# boot.net
KiCad netlist of a schematic drawn in Altium Designer
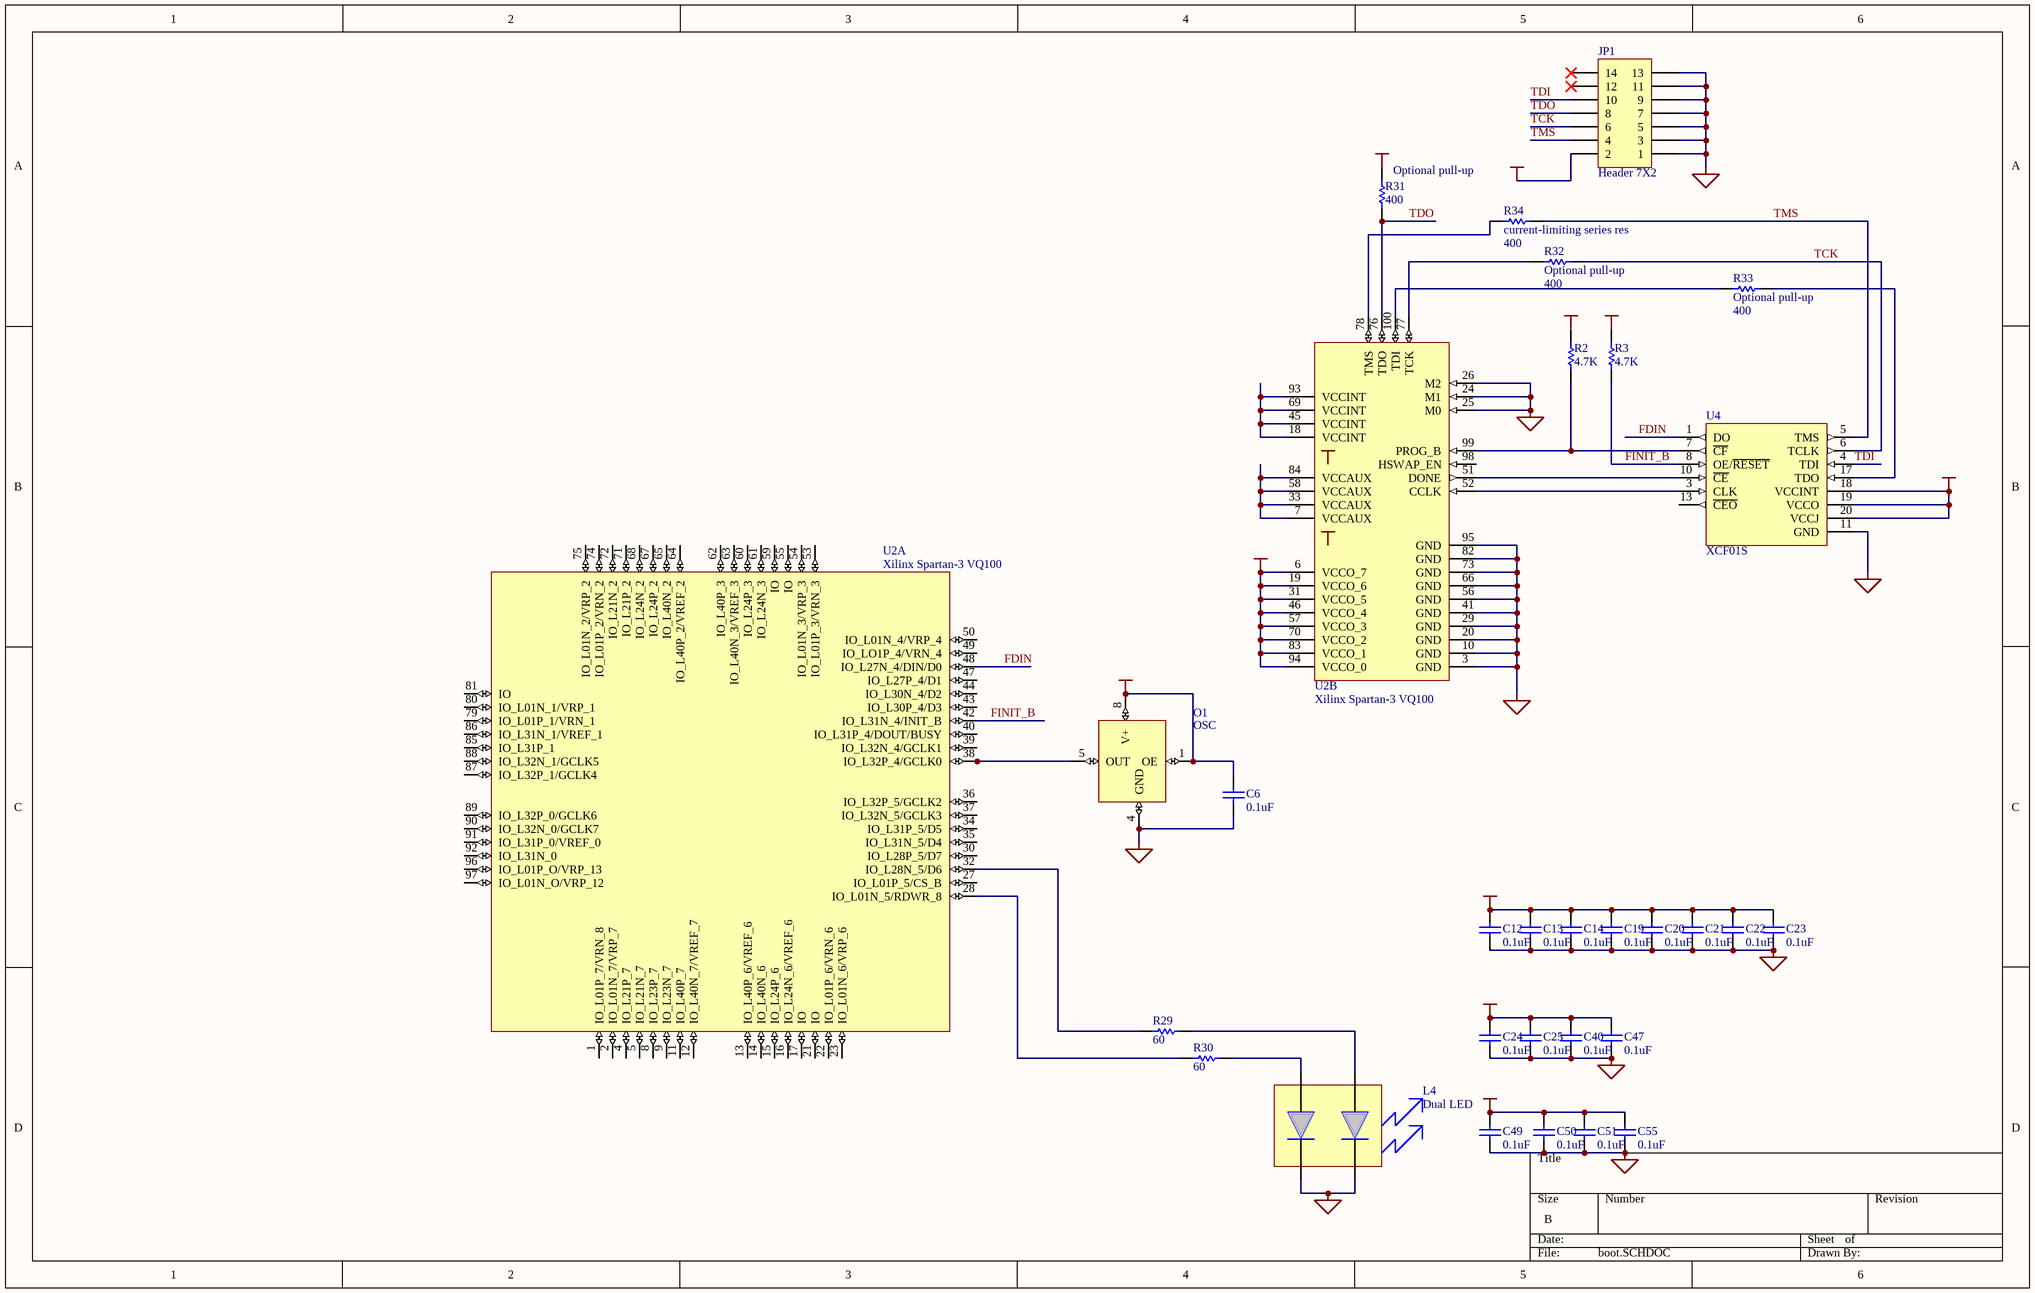
[diagram p0: boot.SCHDOC]

(export (version "E")
  (design (tool "Eeschema 10.0.6"))
  (components
    (comp (ref "C6")
      (value "Cap")
      (footprint "CC1608-0603")
      (description "Capacitor")
      (fields
        (field (name "MANUFACTURER") "Generic Components")
        (field (name "ALTIUM_VALUE") "0.1uF")
        (field (name "PUBLISHER") "Altium Limited")
      )
      (libsource (lib "Miscellaneous Devices") (part "Cap"))
    )
    (comp (ref "C12")
      (value "Cap")
      (footprint "CC1608-0603")
      (description "Capacitor")
      (fields
        (field (name "MANUFACTURER") "Generic Components")
        (field (name "ALTIUM_VALUE") "0.1uF")
        (field (name "PUBLISHER") "Altium Limited")
      )
      (libsource (lib "Miscellaneous Devices") (part "Cap"))
    )
    (comp (ref "C13")
      (value "Cap")
      (footprint "CC1608-0603")
      (description "Capacitor")
      (fields
        (field (name "MANUFACTURER") "Generic Components")
        (field (name "ALTIUM_VALUE") "0.1uF")
        (field (name "PUBLISHER") "Altium Limited")
      )
      (libsource (lib "Miscellaneous Devices") (part "Cap"))
    )
    (comp (ref "C14")
      (value "Cap")
      (footprint "CC1608-0603")
      (description "Capacitor")
      (fields
        (field (name "MANUFACTURER") "Generic Components")
        (field (name "ALTIUM_VALUE") "0.1uF")
        (field (name "PUBLISHER") "Altium Limited")
      )
      (libsource (lib "Miscellaneous Devices") (part "Cap"))
    )
    (comp (ref "C19")
      (value "Cap")
      (footprint "CC1608-0603")
      (description "Capacitor")
      (fields
        (field (name "MANUFACTURER") "Generic Components")
        (field (name "ALTIUM_VALUE") "0.1uF")
        (field (name "PUBLISHER") "Altium Limited")
      )
      (libsource (lib "Miscellaneous Devices") (part "Cap"))
    )
    (comp (ref "C20")
      (value "Cap")
      (footprint "CC1608-0603")
      (description "Capacitor")
      (fields
        (field (name "MANUFACTURER") "Generic Components")
        (field (name "ALTIUM_VALUE") "0.1uF")
        (field (name "PUBLISHER") "Altium Limited")
      )
      (libsource (lib "Miscellaneous Devices") (part "Cap"))
    )
    (comp (ref "C21")
      (value "Cap")
      (footprint "CC1608-0603")
      (description "Capacitor")
      (fields
        (field (name "MANUFACTURER") "Generic Components")
        (field (name "ALTIUM_VALUE") "0.1uF")
        (field (name "PUBLISHER") "Altium Limited")
      )
      (libsource (lib "Miscellaneous Devices") (part "Cap"))
    )
    (comp (ref "C22")
      (value "Cap")
      (footprint "CC1608-0603")
      (description "Capacitor")
      (fields
        (field (name "MANUFACTURER") "Generic Components")
        (field (name "ALTIUM_VALUE") "0.1uF")
        (field (name "PUBLISHER") "Altium Limited")
      )
      (libsource (lib "Miscellaneous Devices") (part "Cap"))
    )
    (comp (ref "C23")
      (value "Cap")
      (footprint "CC1608-0603")
      (description "Capacitor")
      (fields
        (field (name "MANUFACTURER") "Generic Components")
        (field (name "ALTIUM_VALUE") "0.1uF")
        (field (name "PUBLISHER") "Altium Limited")
      )
      (libsource (lib "Miscellaneous Devices") (part "Cap"))
    )
    (comp (ref "C24")
      (value "Cap")
      (footprint "CC1608-0603")
      (description "Capacitor")
      (fields
        (field (name "MANUFACTURER") "Generic Components")
        (field (name "ALTIUM_VALUE") "0.1uF")
        (field (name "PUBLISHER") "Altium Limited")
      )
      (libsource (lib "Miscellaneous Devices") (part "Cap"))
    )
    (comp (ref "C25")
      (value "Cap")
      (footprint "CC1608-0603")
      (description "Capacitor")
      (fields
        (field (name "MANUFACTURER") "Generic Components")
        (field (name "ALTIUM_VALUE") "0.1uF")
        (field (name "PUBLISHER") "Altium Limited")
      )
      (libsource (lib "Miscellaneous Devices") (part "Cap"))
    )
    (comp (ref "C40")
      (value "Cap")
      (footprint "CC1608-0603")
      (description "Capacitor")
      (fields
        (field (name "MANUFACTURER") "Generic Components")
        (field (name "ALTIUM_VALUE") "0.1uF")
        (field (name "PUBLISHER") "Altium Limited")
      )
      (libsource (lib "Miscellaneous Devices") (part "Cap"))
    )
    (comp (ref "C47")
      (value "Cap")
      (footprint "CC1608-0603")
      (description "Capacitor")
      (fields
        (field (name "MANUFACTURER") "Generic Components")
        (field (name "ALTIUM_VALUE") "0.1uF")
        (field (name "PUBLISHER") "Altium Limited")
      )
      (libsource (lib "Miscellaneous Devices") (part "Cap"))
    )
    (comp (ref "C49")
      (value "Cap")
      (footprint "CC1608-0603")
      (description "Capacitor")
      (fields
        (field (name "MANUFACTURER") "Generic Components")
        (field (name "ALTIUM_VALUE") "0.1uF")
        (field (name "PUBLISHER") "Altium Limited")
      )
      (libsource (lib "Miscellaneous Devices") (part "Cap"))
    )
    (comp (ref "C50")
      (value "Cap")
      (footprint "CC1608-0603")
      (description "Capacitor")
      (fields
        (field (name "MANUFACTURER") "Generic Components")
        (field (name "ALTIUM_VALUE") "0.1uF")
        (field (name "PUBLISHER") "Altium Limited")
      )
      (libsource (lib "Miscellaneous Devices") (part "Cap"))
    )
    (comp (ref "C51")
      (value "Cap")
      (footprint "CC1608-0603")
      (description "Capacitor")
      (fields
        (field (name "MANUFACTURER") "Generic Components")
        (field (name "ALTIUM_VALUE") "0.1uF")
        (field (name "PUBLISHER") "Altium Limited")
      )
      (libsource (lib "Miscellaneous Devices") (part "Cap"))
    )
    (comp (ref "C55")
      (value "Cap")
      (footprint "CC1608-0603")
      (description "Capacitor")
      (fields
        (field (name "MANUFACTURER") "Generic Components")
        (field (name "ALTIUM_VALUE") "0.1uF")
        (field (name "PUBLISHER") "Altium Limited")
      )
      (libsource (lib "Miscellaneous Devices") (part "Cap"))
    )
    (comp (ref "JP1")
      (value "Header 7X2")
      (footprint "HDR2X7")
      (description "Header, 7-Pin, Dual row")
      (fields (field (name "MANUFACTURER") "Generic Components") (field (name "PUBLISHER") "Altium Limited"))
      (libsource (lib "Miscellaneous Connectors") (part "Header 7X2"))
    )
    (comp (ref "L4")
      (value "Dual LED")
      (footprint "LUMEX DUAL RT-ANG LED")
      (description "DUAL LED")
      (libsource (lib "My devices") (part "DUAL LED"))
    )
    (comp (ref "O1")
      (value "OSC")
      (footprint "SG636PCE")
      (description "Epson CMOS/TTL Oscillator")
      (libsource (lib "My devices") (part "OSC"))
    )
    (comp (ref "R2")
      (value "Res1")
      (footprint "CC1608-0603")
      (description "Resistor")
      (fields
        (field (name "MANUFACTURER") "Generic Components")
        (field (name "ALTIUM_VALUE") "4.7K")
        (field (name "PUBLISHER") "Altium Limited")
      )
      (libsource (lib "Miscellaneous Devices") (part "Res1"))
    )
    (comp (ref "R3")
      (value "Res1")
      (footprint "CC1608-0603")
      (description "Resistor")
      (fields
        (field (name "MANUFACTURER") "Generic Components")
        (field (name "ALTIUM_VALUE") "4.7K")
        (field (name "PUBLISHER") "Altium Limited")
      )
      (libsource (lib "Miscellaneous Devices") (part "Res1"))
    )
    (comp (ref "R29")
      (value "Res1")
      (footprint "R2012-0805")
      (description "Resistor")
      (fields
        (field (name "MANUFACTURER") "Generic Components")
        (field (name "ALTIUM_VALUE") "60")
        (field (name "PUBLISHER") "Altium Limited")
      )
      (libsource (lib "Miscellaneous Devices") (part "Res1"))
    )
    (comp (ref "R30")
      (value "Res1")
      (footprint "R2012-0805")
      (description "Resistor")
      (fields
        (field (name "MANUFACTURER") "Generic Components")
        (field (name "ALTIUM_VALUE") "60")
        (field (name "PUBLISHER") "Altium Limited")
      )
      (libsource (lib "Miscellaneous Devices") (part "Res1"))
    )
    (comp (ref "R31")
      (value "Optional pull-up")
      (footprint "CC1608-0603")
      (description "Resistor")
      (fields
        (field (name "MANUFACTURER") "Generic Components")
        (field (name "ALTIUM_VALUE") "400")
        (field (name "PUBLISHER") "Altium Limited")
      )
      (libsource (lib "Miscellaneous Devices") (part "Res1"))
    )
    (comp (ref "R32")
      (value "Optional pull-up")
      (footprint "CC1608-0603")
      (description "Resistor")
      (fields
        (field (name "MANUFACTURER") "Generic Components")
        (field (name "ALTIUM_VALUE") "400")
        (field (name "PUBLISHER") "Altium Limited")
      )
      (libsource (lib "Miscellaneous Devices") (part "Res1"))
    )
    (comp (ref "R33")
      (value "Optional pull-up")
      (footprint "CC1608-0603")
      (description "Resistor")
      (fields
        (field (name "MANUFACTURER") "Generic Components")
        (field (name "ALTIUM_VALUE") "400")
        (field (name "PUBLISHER") "Altium Limited")
      )
      (libsource (lib "Miscellaneous Devices") (part "Res1"))
    )
    (comp (ref "R34")
      (value "current-limiting series res")
      (footprint "CC1608-0603")
      (description "Resistor")
      (fields
        (field (name "MANUFACTURER") "Generic Components")
        (field (name "ALTIUM_VALUE") "400")
        (field (name "PUBLISHER") "Altium Limited")
      )
      (libsource (lib "Miscellaneous Devices") (part "Res1"))
    )
    (comp (ref "U2")
      (value "Xilinx Spartan-3 VQ100")
      (footprint "F-QFP14X14-G100/N")
      (libsource (lib "") (part "XC3S50-VQ100_1"))
    )
    (comp (ref "U4")
      (value "XCF01S")
      (footprint "TSSO6x6-G20/X.3")
      (description "Xilinx Platform Flash")
      (libsource (lib "My devices") (part "XCF01S"))
    )
  )
  (nets
    (net (code "1") (name "+1.2VCC") (class "Default")
      (node (ref "C24") (pin "1") (pinfunction "1_1") (pintype "passive"))
      (node (ref "C25") (pin "1") (pinfunction "1_1") (pintype "passive"))
      (node (ref "C40") (pin "1") (pinfunction "1_1") (pintype "passive"))
      (node (ref "C47") (pin "1") (pinfunction "1_1") (pintype "passive"))
    )
    (net (code "2") (name "+2.5VCC") (class "Default")
      (node (ref "C49") (pin "1") (pinfunction "1_1") (pintype "passive"))
      (node (ref "C50") (pin "1") (pinfunction "1_1") (pintype "passive"))
      (node (ref "C51") (pin "1") (pinfunction "1_1") (pintype "passive"))
      (node (ref "C55") (pin "1") (pinfunction "1_1") (pintype "passive"))
    )
    (net (code "3") (name "/FDIN") (class "Default")
      (node (ref "U2") (pin "48") (pinfunction "IO_L27N_4/DIN/D0_48") (pintype "bidirectional"))
      (node (ref "U4") (pin "1") (pinfunction "DO_1") (pintype "output"))
    )
    (net (code "4") (name "/FINIT_B") (class "Default")
      (node (ref "R3") (pin "1") (pinfunction "1_1") (pintype "passive"))
      (node (ref "U2") (pin "42") (pinfunction "IO_L31N_4/INIT_B_42") (pintype "bidirectional"))
      (node (ref "U4") (pin "8") (pinfunction "OE/~{RESET}_8") (pintype "input"))
    )
    (net (code "5") (name "/TCK") (class "Default")
      (node (ref "JP1") (pin "6") (pinfunction "6_6") (pintype "passive"))
      (node (ref "R32") (pin "1") (pinfunction "1_1") (pintype "passive"))
      (node (ref "U4") (pin "6") (pinfunction "TCLK_6") (pintype "output"))
    )
    (net (code "6") (name "/TDI") (class "Default")
      (node (ref "JP1") (pin "10") (pinfunction "10_10") (pintype "passive"))
      (node (ref "U4") (pin "4") (pinfunction "TDI_4") (pintype "input"))
    )
    (net (code "7") (name "/TDO") (class "Default")
      (node (ref "JP1") (pin "8") (pinfunction "8_8") (pintype "passive"))
      (node (ref "R31") (pin "1") (pinfunction "1_1") (pintype "passive"))
      (node (ref "U2") (pin "76") (pinfunction "TDO_76") (pintype "bidirectional"))
    )
    (net (code "8") (name "/TMS") (class "Default")
      (node (ref "JP1") (pin "4") (pinfunction "4_4") (pintype "passive"))
      (node (ref "R34") (pin "1") (pinfunction "1_1") (pintype "passive"))
      (node (ref "U4") (pin "5") (pinfunction "TMS_5") (pintype "output"))
    )
    (net (code "9") (name "GND") (class "Default")
      (node (ref "C12") (pin "2") (pinfunction "2_2") (pintype "passive"))
      (node (ref "C13") (pin "2") (pinfunction "2_2") (pintype "passive"))
      (node (ref "C14") (pin "2") (pinfunction "2_2") (pintype "passive"))
      (node (ref "C19") (pin "2") (pinfunction "2_2") (pintype "passive"))
      (node (ref "C20") (pin "2") (pinfunction "2_2") (pintype "passive"))
      (node (ref "C21") (pin "2") (pinfunction "2_2") (pintype "passive"))
      (node (ref "C22") (pin "2") (pinfunction "2_2") (pintype "passive"))
      (node (ref "C23") (pin "2") (pinfunction "2_2") (pintype "passive"))
      (node (ref "C24") (pin "2") (pinfunction "2_2") (pintype "passive"))
      (node (ref "C25") (pin "2") (pinfunction "2_2") (pintype "passive"))
      (node (ref "C40") (pin "2") (pinfunction "2_2") (pintype "passive"))
      (node (ref "C47") (pin "2") (pinfunction "2_2") (pintype "passive"))
      (node (ref "C49") (pin "2") (pinfunction "2_2") (pintype "passive"))
      (node (ref "C50") (pin "2") (pinfunction "2_2") (pintype "passive"))
      (node (ref "C51") (pin "2") (pinfunction "2_2") (pintype "passive"))
      (node (ref "C55") (pin "2") (pinfunction "2_2") (pintype "passive"))
      (node (ref "C6") (pin "2") (pinfunction "2_2") (pintype "passive"))
      (node (ref "JP1") (pin "1") (pinfunction "1_1") (pintype "passive"))
      (node (ref "JP1") (pin "11") (pinfunction "11_11") (pintype "passive"))
      (node (ref "JP1") (pin "13") (pinfunction "13_13") (pintype "passive"))
      (node (ref "JP1") (pin "3") (pinfunction "3_3") (pintype "passive"))
      (node (ref "JP1") (pin "5") (pinfunction "5_5") (pintype "passive"))
      (node (ref "JP1") (pin "7") (pinfunction "7_7") (pintype "passive"))
      (node (ref "JP1") (pin "9") (pinfunction "9_9") (pintype "passive"))
      (node (ref "L4") (pin "2") (pinfunction "2_2") (pintype "passive"))
      (node (ref "L4") (pin "4") (pinfunction "C2_4") (pintype "passive"))
      (node (ref "O1") (pin "4") (pinfunction "GND_4") (pintype "bidirectional"))
      (node (ref "U2") (pin "10") (pinfunction "GND_10") (pintype "power_in"))
      (node (ref "U2") (pin "20") (pinfunction "GND_20") (pintype "power_in"))
      (node (ref "U2") (pin "24") (pinfunction "M1_24") (pintype "input"))
      (node (ref "U2") (pin "25") (pinfunction "M0_25") (pintype "input"))
      (node (ref "U2") (pin "26") (pinfunction "M2_26") (pintype "input"))
      (node (ref "U2") (pin "29") (pinfunction "GND_29") (pintype "power_in"))
      (node (ref "U2") (pin "3") (pinfunction "GND_3") (pintype "power_in"))
      (node (ref "U2") (pin "41") (pinfunction "GND_41") (pintype "power_in"))
      (node (ref "U2") (pin "56") (pinfunction "GND_56") (pintype "power_in"))
      (node (ref "U2") (pin "66") (pinfunction "GND_66") (pintype "power_in"))
      (node (ref "U2") (pin "73") (pinfunction "GND_73") (pintype "power_in"))
      (node (ref "U2") (pin "82") (pinfunction "GND_82") (pintype "power_in"))
      (node (ref "U2") (pin "95") (pinfunction "GND_95") (pintype "power_in"))
      (node (ref "U4") (pin "11") (pinfunction "GND_11") (pintype "power_in"))
    )
    (net (code "10") (name "Net-(L4-A1)") (class "Default")
      (node (ref "L4") (pin "1") (pinfunction "A1_1") (pintype "passive"))
      (node (ref "R30") (pin "1") (pinfunction "1_1") (pintype "passive"))
    )
    (net (code "11") (name "Net-(L4-A2)") (class "Default")
      (node (ref "L4") (pin "3") (pinfunction "A2_3") (pintype "passive"))
      (node (ref "R29") (pin "1") (pinfunction "1_1") (pintype "passive"))
    )
    (net (code "12") (name "Net-(O1-OUT)") (class "Default")
      (node (ref "O1") (pin "5") (pinfunction "OUT_5") (pintype "bidirectional"))
      (node (ref "U2") (pin "38") (pinfunction "IO_L32P_4/GCLK0_38") (pintype "bidirectional"))
    )
    (net (code "13") (name "Net-(U2A-IO_L01N_5{slash}RDWR_8)") (class "Default")
      (node (ref "R30") (pin "2") (pinfunction "2_2") (pintype "passive"))
      (node (ref "U2") (pin "28") (pinfunction "IO_L01N_5/RDWR_8_28") (pintype "bidirectional"))
    )
    (net (code "14") (name "Net-(U2A-IO_L28N_5{slash}D6)") (class "Default")
      (node (ref "R29") (pin "2") (pinfunction "2_2") (pintype "passive"))
      (node (ref "U2") (pin "32") (pinfunction "IO_L28N_5/D6_32") (pintype "bidirectional"))
    )
    (net (code "15") (name "Net-(U2B-CCLK)") (class "Default")
      (node (ref "U2") (pin "52") (pinfunction "CCLK_52") (pintype "input"))
      (node (ref "U4") (pin "3") (pinfunction "CLK_3") (pintype "input"))
    )
    (net (code "16") (name "Net-(U2B-DONE)") (class "Default")
      (node (ref "U2") (pin "51") (pinfunction "DONE_51") (pintype "output"))
      (node (ref "U4") (pin "10") (pinfunction "~{CE}_10") (pintype "input"))
    )
    (net (code "17") (name "Net-(U2B-PROG_B)") (class "Default")
      (node (ref "R2") (pin "1") (pinfunction "1_1") (pintype "passive"))
      (node (ref "U2") (pin "99") (pinfunction "PROG_B_99") (pintype "input"))
      (node (ref "U4") (pin "7") (pinfunction "~{CF}_7") (pintype "output"))
    )
    (net (code "18") (name "Net-(U2B-TCK)") (class "Default")
      (node (ref "R32") (pin "2") (pinfunction "2_2") (pintype "passive"))
      (node (ref "U2") (pin "77") (pinfunction "TCK_77") (pintype "bidirectional"))
    )
    (net (code "19") (name "Net-(U2B-TDI)") (class "Default")
      (node (ref "R33") (pin "2") (pinfunction "2_2") (pintype "passive"))
      (node (ref "U2") (pin "100") (pinfunction "TDI_100") (pintype "bidirectional"))
    )
    (net (code "20") (name "Net-(U2B-TMS)") (class "Default")
      (node (ref "R34") (pin "2") (pinfunction "2_2") (pintype "passive"))
      (node (ref "U2") (pin "78") (pinfunction "TMS_78") (pintype "bidirectional"))
    )
    (net (code "21") (name "Net-(U2B-VCCAUX-Pad33)") (class "Default")
      (node (ref "U2") (pin "33") (pinfunction "VCCAUX_33") (pintype "power_in"))
      (node (ref "U2") (pin "58") (pinfunction "VCCAUX_58") (pintype "power_in"))
      (node (ref "U2") (pin "7") (pinfunction "VCCAUX_7") (pintype "power_in"))
      (node (ref "U2") (pin "84") (pinfunction "VCCAUX_84") (pintype "power_in"))
    )
    (net (code "22") (name "Net-(U2B-VCCINT-Pad18)") (class "Default")
      (node (ref "U2") (pin "18") (pinfunction "VCCINT_18") (pintype "power_in"))
      (node (ref "U2") (pin "45") (pinfunction "VCCINT_45") (pintype "power_in"))
      (node (ref "U2") (pin "69") (pinfunction "VCCINT_69") (pintype "power_in"))
      (node (ref "U2") (pin "93") (pinfunction "VCCINT_93") (pintype "power_in"))
    )
    (net (code "23") (name "Net-(U4-TDO)") (class "Default")
      (node (ref "R33") (pin "1") (pinfunction "1_1") (pintype "passive"))
      (node (ref "U4") (pin "17") (pinfunction "TDO_17") (pintype "input"))
    )
    (net (code "24") (name "VCC") (class "Default")
      (node (ref "C12") (pin "1") (pinfunction "1_1") (pintype "passive"))
      (node (ref "C13") (pin "1") (pinfunction "1_1") (pintype "passive"))
      (node (ref "C14") (pin "1") (pinfunction "1_1") (pintype "passive"))
      (node (ref "C19") (pin "1") (pinfunction "1_1") (pintype "passive"))
      (node (ref "C20") (pin "1") (pinfunction "1_1") (pintype "passive"))
      (node (ref "C21") (pin "1") (pinfunction "1_1") (pintype "passive"))
      (node (ref "C22") (pin "1") (pinfunction "1_1") (pintype "passive"))
      (node (ref "C23") (pin "1") (pinfunction "1_1") (pintype "passive"))
      (node (ref "C6") (pin "1") (pinfunction "1_1") (pintype "passive"))
      (node (ref "JP1") (pin "2") (pinfunction "2_2") (pintype "passive"))
      (node (ref "O1") (pin "1") (pinfunction "OE_1") (pintype "bidirectional"))
      (node (ref "O1") (pin "8") (pinfunction "V+_8") (pintype "bidirectional"))
      (node (ref "R2") (pin "2") (pinfunction "2_2") (pintype "passive"))
      (node (ref "R3") (pin "2") (pinfunction "2_2") (pintype "passive"))
      (node (ref "R31") (pin "2") (pinfunction "2_2") (pintype "passive"))
      (node (ref "U2") (pin "19") (pinfunction "VCCO_6_19") (pintype "power_in"))
      (node (ref "U2") (pin "31") (pinfunction "VCCO_5_31") (pintype "power_in"))
      (node (ref "U2") (pin "46") (pinfunction "VCCO_4_46") (pintype "power_in"))
      (node (ref "U2") (pin "57") (pinfunction "VCCO_3_57") (pintype "power_in"))
      (node (ref "U2") (pin "6") (pinfunction "VCCO_7_6") (pintype "power_in"))
      (node (ref "U2") (pin "70") (pinfunction "VCCO_2_70") (pintype "power_in"))
      (node (ref "U2") (pin "83") (pinfunction "VCCO_1_83") (pintype "power_in"))
      (node (ref "U2") (pin "94") (pinfunction "VCCO_0_94") (pintype "power_in"))
      (node (ref "U4") (pin "18") (pinfunction "VCCINT_18") (pintype "power_in"))
      (node (ref "U4") (pin "19") (pinfunction "VCCO_19") (pintype "power_in"))
      (node (ref "U4") (pin "20") (pinfunction "VCCJ_20") (pintype "power_in"))
    )
    (net (code "25") (name "unconnected-(JP1-Pad12)") (class "Default")
      (node (ref "JP1") (pin "12") (pinfunction "12_12") (pintype "passive+no_connect"))
    )
    (net (code "26") (name "unconnected-(JP1-Pad14)") (class "Default")
      (node (ref "JP1") (pin "14") (pinfunction "14_14") (pintype "passive+no_connect"))
    )
    (net (code "27") (name "unconnected-(U2A-IO-Pad17)") (class "Default")
      (node (ref "U2") (pin "17") (pinfunction "IO_17") (pintype "bidirectional"))
    )
    (net (code "28") (name "unconnected-(U2A-IO-Pad21)") (class "Default")
      (node (ref "U2") (pin "21") (pinfunction "IO_21") (pintype "bidirectional"))
    )
    (net (code "29") (name "unconnected-(U2A-IO-Pad55)") (class "Default")
      (node (ref "U2") (pin "55") (pinfunction "IO_55") (pintype "bidirectional"))
    )
    (net (code "30") (name "unconnected-(U2A-IO-Pad59)") (class "Default")
      (node (ref "U2") (pin "59") (pinfunction "IO_59") (pintype "bidirectional"))
    )
    (net (code "31") (name "unconnected-(U2A-IO-Pad81)") (class "Default")
      (node (ref "U2") (pin "81") (pinfunction "IO_81") (pintype "bidirectional"))
    )
    (net (code "32") (name "unconnected-(U2A-IO_L01N_1{slash}VRP_1-Pad80)") (class "Default")
      (node (ref "U2") (pin "80") (pinfunction "IO_L01N_1/VRP_1_80") (pintype "bidirectional"))
    )
    (net (code "33") (name "unconnected-(U2A-IO_L01N_2{slash}VRP_2-Pad75)") (class "Default")
      (node (ref "U2") (pin "75") (pinfunction "IO_L01N_2/VRP_2_75") (pintype "bidirectional"))
    )
    (net (code "34") (name "unconnected-(U2A-IO_L01N_3{slash}VRP_3-Pad54)") (class "Default")
      (node (ref "U2") (pin "54") (pinfunction "IO_L01N_3/VRP_3_54") (pintype "bidirectional"))
    )
    (net (code "35") (name "unconnected-(U2A-IO_L01N_4{slash}VRP_4-Pad50)") (class "Default")
      (node (ref "U2") (pin "50") (pinfunction "IO_L01N_4/VRP_4_50") (pintype "bidirectional"))
    )
    (net (code "36") (name "unconnected-(U2A-IO_L01N_6{slash}VRP_6-Pad23)") (class "Default")
      (node (ref "U2") (pin "23") (pinfunction "IO_L01N_6/VRP_6_23") (pintype "bidirectional"))
    )
    (net (code "37") (name "unconnected-(U2A-IO_L01N_7{slash}VRP_7-Pad2)") (class "Default")
      (node (ref "U2") (pin "2") (pinfunction "IO_L01N_7/VRP_7_2") (pintype "bidirectional"))
    )
    (net (code "38") (name "unconnected-(U2A-IO_L01N_O{slash}VRP_12-Pad97)") (class "Default")
      (node (ref "U2") (pin "97") (pinfunction "IO_L01N_O/VRP_12_97") (pintype "bidirectional"))
    )
    (net (code "39") (name "unconnected-(U2A-IO_L01P_1{slash}VRN_1-Pad79)") (class "Default")
      (node (ref "U2") (pin "79") (pinfunction "IO_L01P_1/VRN_1_79") (pintype "bidirectional"))
    )
    (net (code "40") (name "unconnected-(U2A-IO_L01P_2{slash}VRN_2-Pad74)") (class "Default")
      (node (ref "U2") (pin "74") (pinfunction "IO_L01P_2/VRN_2_74") (pintype "bidirectional"))
    )
    (net (code "41") (name "unconnected-(U2A-IO_L01P_3{slash}VRN_3-Pad53)") (class "Default")
      (node (ref "U2") (pin "53") (pinfunction "IO_L01P_3/VRN_3_53") (pintype "bidirectional"))
    )
    (net (code "42") (name "unconnected-(U2A-IO_L01P_5{slash}CS_B-Pad27)") (class "Default")
      (node (ref "U2") (pin "27") (pinfunction "IO_L01P_5/CS_B_27") (pintype "bidirectional"))
    )
    (net (code "43") (name "unconnected-(U2A-IO_L01P_6{slash}VRN_6-Pad22)") (class "Default")
      (node (ref "U2") (pin "22") (pinfunction "IO_L01P_6/VRN_6_22") (pintype "bidirectional"))
    )
    (net (code "44") (name "unconnected-(U2A-IO_L01P_7{slash}VRN_8-Pad1)") (class "Default")
      (node (ref "U2") (pin "1") (pinfunction "IO_L01P_7/VRN_8_1") (pintype "bidirectional"))
    )
    (net (code "45") (name "unconnected-(U2A-IO_L01P_O{slash}VRP_13-Pad96)") (class "Default")
      (node (ref "U2") (pin "96") (pinfunction "IO_L01P_O/VRP_13_96") (pintype "bidirectional"))
    )
    (net (code "46") (name "unconnected-(U2A-IO_L21N_2-Pad72)") (class "Default")
      (node (ref "U2") (pin "72") (pinfunction "IO_L21N_2_72") (pintype "bidirectional"))
    )
    (net (code "47") (name "unconnected-(U2A-IO_L21N_7-Pad5)") (class "Default")
      (node (ref "U2") (pin "5") (pinfunction "IO_L21N_7_5") (pintype "bidirectional"))
    )
    (net (code "48") (name "unconnected-(U2A-IO_L21P_2-Pad71)") (class "Default")
      (node (ref "U2") (pin "71") (pinfunction "IO_L21P_2_71") (pintype "bidirectional"))
    )
    (net (code "49") (name "unconnected-(U2A-IO_L21P_7-Pad4)") (class "Default")
      (node (ref "U2") (pin "4") (pinfunction "IO_L21P_7_4") (pintype "bidirectional"))
    )
    (net (code "50") (name "unconnected-(U2A-IO_L23N_7-Pad9)") (class "Default")
      (node (ref "U2") (pin "9") (pinfunction "IO_L23N_7_9") (pintype "bidirectional"))
    )
    (net (code "51") (name "unconnected-(U2A-IO_L23P_7-Pad8)") (class "Default")
      (node (ref "U2") (pin "8") (pinfunction "IO_L23P_7_8") (pintype "bidirectional"))
    )
    (net (code "52") (name "unconnected-(U2A-IO_L24N_2-Pad68)") (class "Default")
      (node (ref "U2") (pin "68") (pinfunction "IO_L24N_2_68") (pintype "bidirectional"))
    )
    (net (code "53") (name "unconnected-(U2A-IO_L24N_3-Pad61)") (class "Default")
      (node (ref "U2") (pin "61") (pinfunction "IO_L24N_3_61") (pintype "bidirectional"))
    )
    (net (code "54") (name "unconnected-(U2A-IO_L24N_6{slash}VREF_6-Pad16)") (class "Default")
      (node (ref "U2") (pin "16") (pinfunction "IO_L24N_6/VREF_6_16") (pintype "bidirectional"))
    )
    (net (code "55") (name "unconnected-(U2A-IO_L24P_2-Pad67)") (class "Default")
      (node (ref "U2") (pin "67") (pinfunction "IO_L24P_2_67") (pintype "bidirectional"))
    )
    (net (code "56") (name "unconnected-(U2A-IO_L24P_3-Pad60)") (class "Default")
      (node (ref "U2") (pin "60") (pinfunction "IO_L24P_3_60") (pintype "bidirectional"))
    )
    (net (code "57") (name "unconnected-(U2A-IO_L24P_6-Pad15)") (class "Default")
      (node (ref "U2") (pin "15") (pinfunction "IO_L24P_6_15") (pintype "bidirectional"))
    )
    (net (code "58") (name "unconnected-(U2A-IO_L27P_4{slash}D1-Pad47)") (class "Default")
      (node (ref "U2") (pin "47") (pinfunction "IO_L27P_4/D1_47") (pintype "bidirectional"))
    )
    (net (code "59") (name "unconnected-(U2A-IO_L28P_5{slash}D7-Pad30)") (class "Default")
      (node (ref "U2") (pin "30") (pinfunction "IO_L28P_5/D7_30") (pintype "bidirectional"))
    )
    (net (code "60") (name "unconnected-(U2A-IO_L30N_4{slash}D2-Pad44)") (class "Default")
      (node (ref "U2") (pin "44") (pinfunction "IO_L30N_4/D2_44") (pintype "bidirectional"))
    )
    (net (code "61") (name "unconnected-(U2A-IO_L30P_4{slash}D3-Pad43)") (class "Default")
      (node (ref "U2") (pin "43") (pinfunction "IO_L30P_4/D3_43") (pintype "bidirectional"))
    )
    (net (code "62") (name "unconnected-(U2A-IO_L31N_0-Pad92)") (class "Default")
      (node (ref "U2") (pin "92") (pinfunction "IO_L31N_0_92") (pintype "bidirectional"))
    )
    (net (code "63") (name "unconnected-(U2A-IO_L31N_1{slash}VREF_1-Pad86)") (class "Default")
      (node (ref "U2") (pin "86") (pinfunction "IO_L31N_1/VREF_1_86") (pintype "bidirectional"))
    )
    (net (code "64") (name "unconnected-(U2A-IO_L31N_5{slash}D4-Pad35)") (class "Default")
      (node (ref "U2") (pin "35") (pinfunction "IO_L31N_5/D4_35") (pintype "bidirectional"))
    )
    (net (code "65") (name "unconnected-(U2A-IO_L31P_0{slash}VREF_0-Pad91)") (class "Default")
      (node (ref "U2") (pin "91") (pinfunction "IO_L31P_0/VREF_0_91") (pintype "bidirectional"))
    )
    (net (code "66") (name "unconnected-(U2A-IO_L31P_1-Pad85)") (class "Default")
      (node (ref "U2") (pin "85") (pinfunction "IO_L31P_1_85") (pintype "bidirectional"))
    )
    (net (code "67") (name "unconnected-(U2A-IO_L31P_4{slash}DOUT{slash}BUSY-Pad40)") (class "Default")
      (node (ref "U2") (pin "40") (pinfunction "IO_L31P_4/DOUT/BUSY_40") (pintype "bidirectional"))
    )
    (net (code "68") (name "unconnected-(U2A-IO_L31P_5{slash}D5-Pad34)") (class "Default")
      (node (ref "U2") (pin "34") (pinfunction "IO_L31P_5/D5_34") (pintype "bidirectional"))
    )
    (net (code "69") (name "unconnected-(U2A-IO_L32N_0{slash}GCLK7-Pad90)") (class "Default")
      (node (ref "U2") (pin "90") (pinfunction "IO_L32N_0/GCLK7_90") (pintype "bidirectional"))
    )
    (net (code "70") (name "unconnected-(U2A-IO_L32N_1{slash}GCLK5-Pad88)") (class "Default")
      (node (ref "U2") (pin "88") (pinfunction "IO_L32N_1/GCLK5_88") (pintype "bidirectional"))
    )
    (net (code "71") (name "unconnected-(U2A-IO_L32N_4{slash}GCLK1-Pad39)") (class "Default")
      (node (ref "U2") (pin "39") (pinfunction "IO_L32N_4/GCLK1_39") (pintype "bidirectional"))
    )
    (net (code "72") (name "unconnected-(U2A-IO_L32N_5{slash}GCLK3-Pad37)") (class "Default")
      (node (ref "U2") (pin "37") (pinfunction "IO_L32N_5/GCLK3_37") (pintype "bidirectional"))
    )
    (net (code "73") (name "unconnected-(U2A-IO_L32P_0{slash}GCLK6-Pad89)") (class "Default")
      (node (ref "U2") (pin "89") (pinfunction "IO_L32P_0/GCLK6_89") (pintype "bidirectional"))
    )
    (net (code "74") (name "unconnected-(U2A-IO_L32P_1{slash}GCLK4-Pad87)") (class "Default")
      (node (ref "U2") (pin "87") (pinfunction "IO_L32P_1/GCLK4_87") (pintype "bidirectional"))
    )
    (net (code "75") (name "unconnected-(U2A-IO_L32P_5{slash}GCLK2-Pad36)") (class "Default")
      (node (ref "U2") (pin "36") (pinfunction "IO_L32P_5/GCLK2_36") (pintype "bidirectional"))
    )
    (net (code "76") (name "unconnected-(U2A-IO_L40N_2-Pad65)") (class "Default")
      (node (ref "U2") (pin "65") (pinfunction "IO_L40N_2_65") (pintype "bidirectional"))
    )
    (net (code "77") (name "unconnected-(U2A-IO_L40N_3{slash}VREF_3-Pad63)") (class "Default")
      (node (ref "U2") (pin "63") (pinfunction "IO_L40N_3/VREF_3_63") (pintype "bidirectional"))
    )
    (net (code "78") (name "unconnected-(U2A-IO_L40N_6-Pad14)") (class "Default")
      (node (ref "U2") (pin "14") (pinfunction "IO_L40N_6_14") (pintype "bidirectional"))
    )
    (net (code "79") (name "unconnected-(U2A-IO_L40N_7{slash}VREF_7-Pad12)") (class "Default")
      (node (ref "U2") (pin "12") (pinfunction "IO_L40N_7/VREF_7_12") (pintype "bidirectional"))
    )
    (net (code "80") (name "unconnected-(U2A-IO_L40P_2{slash}VREF_2-Pad64)") (class "Default")
      (node (ref "U2") (pin "64") (pinfunction "IO_L40P_2/VREF_2_64") (pintype "bidirectional"))
    )
    (net (code "81") (name "unconnected-(U2A-IO_L40P_3-Pad62)") (class "Default")
      (node (ref "U2") (pin "62") (pinfunction "IO_L40P_3_62") (pintype "bidirectional"))
    )
    (net (code "82") (name "unconnected-(U2A-IO_L40P_6{slash}VREF_6-Pad13)") (class "Default")
      (node (ref "U2") (pin "13") (pinfunction "IO_L40P_6/VREF_6_13") (pintype "bidirectional"))
    )
    (net (code "83") (name "unconnected-(U2A-IO_L40P_7-Pad11)") (class "Default")
      (node (ref "U2") (pin "11") (pinfunction "IO_L40P_7_11") (pintype "bidirectional"))
    )
    (net (code "84") (name "unconnected-(U2A-IO_LO1P_4{slash}VRN_4-Pad49)") (class "Default")
      (node (ref "U2") (pin "49") (pinfunction "IO_LO1P_4/VRN_4_49") (pintype "bidirectional"))
    )
    (net (code "85") (name "unconnected-(U2B-HSWAP_EN-Pad98)") (class "Default")
      (node (ref "U2") (pin "98") (pinfunction "HSWAP_EN_98") (pintype "input"))
    )
    (net (code "86") (name "unconnected-(U4-~{CEO}-Pad13)") (class "Default")
      (node (ref "U4") (pin "13") (pinfunction "~{CEO}_13") (pintype "output"))
    )
  )
)
